# sb-sonata-debug.net
KiCad netlist of a schematic drawn in Altium Designer
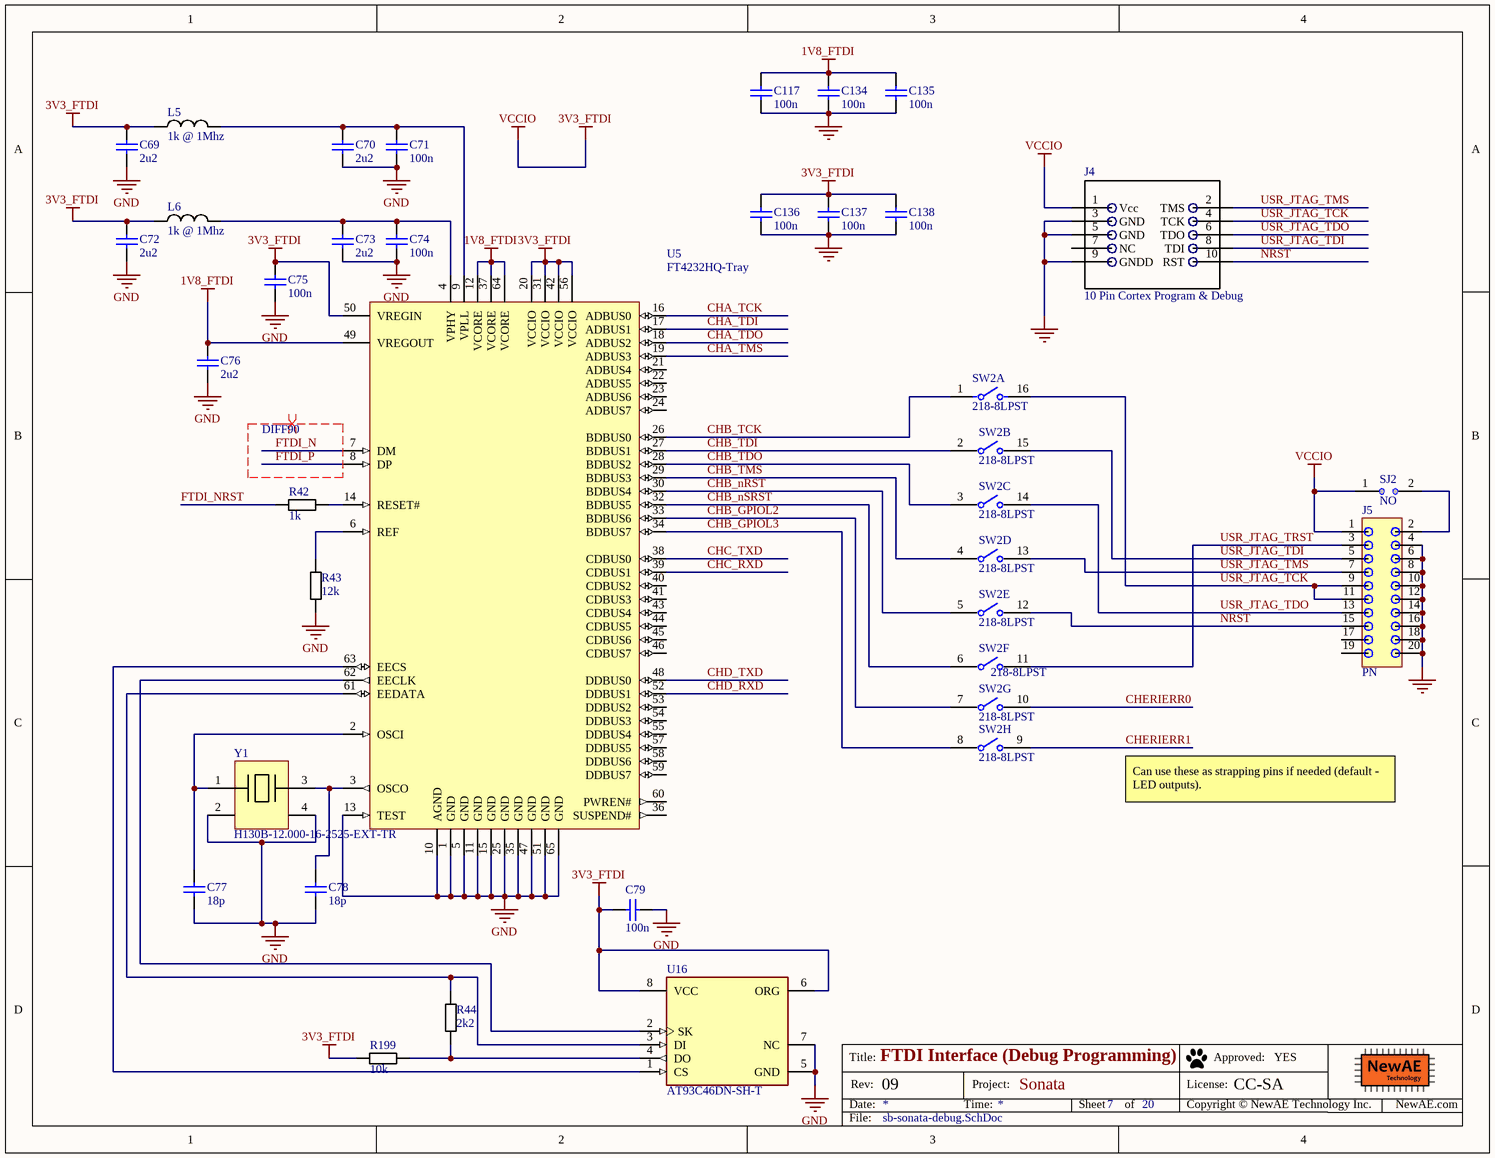
[diagram p0: sb-sonata-debug.SchDoc]

(export (version "E")
  (design (tool "Eeschema 10.0.6"))
  (components
    (comp (ref "C69")
      (value "2u2")
      (footprint "CAPC0603_M")
      (description "2u2, 0603")
      (fields (field (name "PART NUMBER") "CCHIP-2u2-0603"))
      (libsource (lib "NewAE_AltiumLib") (part "CAP"))
    )
    (comp (ref "C70")
      (value "2u2")
      (footprint "CAPC0603_M")
      (description "2u2, 0603")
      (fields (field (name "PART NUMBER") "CCHIP-2u2-0603"))
      (libsource (lib "NewAE_AltiumLib") (part "CAP"))
    )
    (comp (ref "C71")
      (value "100n")
      (footprint "CAPC0402_M")
      (description "100n, 0402")
      (fields (field (name "PART NUMBER") "CCHIP-100n-0402"))
      (libsource (lib "NewAE_AltiumLib") (part "CAP"))
    )
    (comp (ref "C72")
      (value "2u2")
      (footprint "CAPC0603_M")
      (description "2u2, 0603")
      (fields (field (name "PART NUMBER") "CCHIP-2u2-0603"))
      (libsource (lib "NewAE_AltiumLib") (part "CAP"))
    )
    (comp (ref "C73")
      (value "2u2")
      (footprint "CAPC0603_M")
      (description "2u2, 0603")
      (fields (field (name "PART NUMBER") "CCHIP-2u2-0603"))
      (libsource (lib "NewAE_AltiumLib") (part "CAP"))
    )
    (comp (ref "C74")
      (value "100n")
      (footprint "CAPC0402_M")
      (description "100n, 0402")
      (fields (field (name "PART NUMBER") "CCHIP-100n-0402"))
      (libsource (lib "NewAE_AltiumLib") (part "CAP"))
    )
    (comp (ref "C75")
      (value "100n")
      (footprint "CAPC0402_M")
      (description "100n, 0402")
      (fields (field (name "PART NUMBER") "CCHIP-100n-0402"))
      (libsource (lib "NewAE_AltiumLib") (part "CAP"))
    )
    (comp (ref "C76")
      (value "2u2")
      (footprint "CAPC0603_M")
      (description "2u2, 0603")
      (fields (field (name "PART NUMBER") "CCHIP-2u2-0603"))
      (libsource (lib "NewAE_AltiumLib") (part "CAP"))
    )
    (comp (ref "C77")
      (value "18p")
      (footprint "CAPC0402_M")
      (description "18p, 0402")
      (fields (field (name "PART NUMBER") "CCHIP-18p-0402"))
      (libsource (lib "NewAE_AltiumLib") (part "CAP"))
    )
    (comp (ref "C78")
      (value "18p")
      (footprint "CAPC0402_M")
      (description "18p, 0402")
      (fields (field (name "PART NUMBER") "CCHIP-18p-0402"))
      (libsource (lib "NewAE_AltiumLib") (part "CAP"))
    )
    (comp (ref "C79")
      (value "100n")
      (footprint "CAPC0402_M")
      (description "100n, 0402")
      (fields (field (name "PART NUMBER") "CCHIP-100n-0402"))
      (libsource (lib "NewAE_AltiumLib") (part "CAP"))
    )
    (comp (ref "C117")
      (value "100n")
      (footprint "CAPC0402_M")
      (description "100n, 0402")
      (fields (field (name "PART NUMBER") "CCHIP-100n-0402"))
      (libsource (lib "NewAE_AltiumLib") (part "CAP"))
    )
    (comp (ref "C134")
      (value "100n")
      (footprint "CAPC0402_M")
      (description "100n, 0402")
      (fields (field (name "PART NUMBER") "CCHIP-100n-0402"))
      (libsource (lib "NewAE_AltiumLib") (part "CAP"))
    )
    (comp (ref "C135")
      (value "100n")
      (footprint "CAPC0402_M")
      (description "100n, 0402")
      (fields (field (name "PART NUMBER") "CCHIP-100n-0402"))
      (libsource (lib "NewAE_AltiumLib") (part "CAP"))
    )
    (comp (ref "C136")
      (value "100n")
      (footprint "CAPC0402_M")
      (description "100n, 0402")
      (fields (field (name "PART NUMBER") "CCHIP-100n-0402"))
      (libsource (lib "NewAE_AltiumLib") (part "CAP"))
    )
    (comp (ref "C137")
      (value "100n")
      (footprint "CAPC0402_M")
      (description "100n, 0402")
      (fields (field (name "PART NUMBER") "CCHIP-100n-0402"))
      (libsource (lib "NewAE_AltiumLib") (part "CAP"))
    )
    (comp (ref "C138")
      (value "100n")
      (footprint "CAPC0402_M")
      (description "100n, 0402")
      (fields (field (name "PART NUMBER") "CCHIP-100n-0402"))
      (libsource (lib "NewAE_AltiumLib") (part "CAP"))
    )
    (comp (ref "J4")
      (value "10 Pin Cortex Program & Debug")
      (footprint "0.5mm_SMD_Header_5x2")
      (description "10 Pin Cortex Program & Debug 0.5mm pitch")
      (fields (field (name "PART NUMBER") "Cortex_Debug_Header_10Pin"))
      (libsource (lib "NewAE_AltiumLib") (part "Cortex_Debug_Header_10Pin"))
    )
    (comp (ref "J5")
      (value "PN")
      (footprint "CONN_10x2_SHROUDED_2.54mm")
      (description "Header, 2-Row, 20-pin, 0.1\"")
      (fields (field (name "PART NUMBER") "CONN20_2ROW"))
      (libsource (lib "NewAE_AltiumLib") (part "CON20_2ROW"))
    )
    (comp (ref "L5")
      (value "1k @ 1Mhz")
      (footprint "IND_0603")
      (description "Ferrite Beads HI CUR CHIP BD 0603 1000OHMS 25%")
      (fields (field (name "PART NUMBER") "FBCHIP-1k-0603"))
      (libsource (lib "NewAE_AltiumLib") (part "IND"))
    )
    (comp (ref "L6")
      (value "1k @ 1Mhz")
      (footprint "IND_0603")
      (description "Ferrite Beads HI CUR CHIP BD 0603 1000OHMS 25%")
      (fields (field (name "PART NUMBER") "FBCHIP-1k-0603"))
      (libsource (lib "NewAE_AltiumLib") (part "IND"))
    )
    (comp (ref "R42")
      (value "1k")
      (footprint "RESC1005X40N")
      (description "1k res, 0402, 1%, 1/16W")
      (fields (field (name "PART NUMBER") "RCHIP-1K-0402") (field (name "TOLERANCE") "1%"))
      (libsource (lib "") (part "RES-EU_2"))
    )
    (comp (ref "R43")
      (value "12k")
      (footprint "RESC1608X55N")
      (description "12k res, 0603, 1%, 1/10W")
      (fields (field (name "PART NUMBER") "RCHIP-12K-0603") (field (name "TOLERANCE") "1%"))
      (libsource (lib "NewAE_AltiumLib") (part "RES-EU"))
    )
    (comp (ref "R44")
      (value "2k2")
      (footprint "RESC1005X40N")
      (description "2k2 res, 0402, 1%, 1/16W")
      (fields (field (name "PART NUMBER") "RCHIP-2K2-0402") (field (name "TOLERANCE") "1%"))
      (libsource (lib "NewAE_AltiumLib") (part "RES-EU"))
    )
    (comp (ref "R199")
      (value "10k")
      (footprint "RESC1005X40N")
      (description "10k res, 0402, 1%, 1/16W")
      (fields (field (name "PART NUMBER") "RCHIP-10K-0402") (field (name "TOLERANCE") "1%"))
      (libsource (lib "") (part "RES-EU_1"))
    )
    (comp (ref "SJ2")
      (value "NO")
      (footprint "SJ_2S_NO")
      (description "Solder Jumper, NO")
      (fields (field (name "PART NUMBER") "SJ_2S_NO"))
      (libsource (lib "NewAE_AltiumLib") (part "SJ_2S_NO"))
    )
    (comp (ref "SW2")
      (value "218-8LPST")
      (footprint "FP-218-8LPST-MFG")
      (description "SWITCH SLIDE DIP SPST 25MA 24V")
      (libsource (lib "Altium Content Vault") (part "c442af63ff53b934e43635f80d8690e"))
    )
    (comp (ref "U5")
      (value "FT4232HQ-Tray")
      (footprint "QFN64_2_N")
      (description "Quad High Speed USB To Multipurpose UART/MPSSE IC, 64-pin QFN, Tray")
      (fields (field (name "MANUFACTURER") "FTDI"))
      (libsource (lib "Altium Content Vault") (part "COM-UART-FT4232H-QFN64"))
    )
    (comp (ref "U16")
      (value "AT93C46DN-SH-T")
      (footprint "FP-C04-057-SN-MFG")
      (description "IC EEPROM 1K SPI 2MHZ 8SOIC")
      (fields
        (field (name "MANUFACTURER") "Microchip")
        (field (name "OCTOPART") "https://octopart.com/at93c46dn-sh-t-microchip-77759177")
      )
      (libsource (lib "Altium Content Vault") (part "8bb9afc094b350e480db350c7247e52"))
    )
    (comp (ref "Y1")
      (value "H130B-12.000-16-2525-EXT-TR")
      (footprint "5x3.2MM XTAL")
      (description "12MHz ±25ppm Crystal 16pF 35 Ohms 4-SMD, No Lead")
      (fields (field (name "MANUFACTURER PART NUMBER") "H130B-12.000-16-2525-EXT-TR"))
      (libsource (lib "NewAE_AltiumLib") (part "H130B-12.000-16-2525-EXT-TR"))
    )
  )
  (nets
    (net (code "1") (name "/CHA_TCK") (class "Default")
      (node (ref "U5") (pin "16") (pinfunction "ADBUS0_16") (pintype "bidirectional"))
    )
    (net (code "2") (name "/CHA_TDI") (class "Default")
      (node (ref "U5") (pin "17") (pinfunction "ADBUS1_17") (pintype "bidirectional"))
    )
    (net (code "3") (name "/CHA_TDO") (class "Default")
      (node (ref "U5") (pin "18") (pinfunction "ADBUS2_18") (pintype "bidirectional"))
    )
    (net (code "4") (name "/CHA_TMS") (class "Default")
      (node (ref "U5") (pin "19") (pinfunction "ADBUS3_19") (pintype "bidirectional"))
    )
    (net (code "5") (name "/CHB_GPIOL2") (class "Default")
      (node (ref "SW2") (pin "7") (pinfunction "7_7") (pintype "passive"))
      (node (ref "U5") (pin "33") (pinfunction "BDBUS6_33") (pintype "bidirectional"))
    )
    (net (code "6") (name "/CHB_GPIOL3") (class "Default")
      (node (ref "SW2") (pin "8") (pinfunction "8_8") (pintype "passive"))
      (node (ref "U5") (pin "34") (pinfunction "BDBUS7_34") (pintype "bidirectional"))
    )
    (net (code "7") (name "/CHB_TCK") (class "Default")
      (node (ref "SW2") (pin "1") (pinfunction "1_1") (pintype "passive"))
      (node (ref "U5") (pin "26") (pinfunction "BDBUS0_26") (pintype "bidirectional"))
    )
    (net (code "8") (name "/CHB_TDI") (class "Default")
      (node (ref "SW2") (pin "2") (pinfunction "2_2") (pintype "passive"))
      (node (ref "U5") (pin "27") (pinfunction "BDBUS1_27") (pintype "bidirectional"))
    )
    (net (code "9") (name "/CHB_TDO") (class "Default")
      (node (ref "SW2") (pin "3") (pinfunction "3_3") (pintype "passive"))
      (node (ref "U5") (pin "28") (pinfunction "BDBUS2_28") (pintype "bidirectional"))
    )
    (net (code "10") (name "/CHB_TMS") (class "Default")
      (node (ref "SW2") (pin "4") (pinfunction "4_4") (pintype "passive"))
      (node (ref "U5") (pin "29") (pinfunction "BDBUS3_29") (pintype "bidirectional"))
    )
    (net (code "11") (name "/CHB_nRST") (class "Default")
      (node (ref "SW2") (pin "5") (pinfunction "5_5") (pintype "passive"))
      (node (ref "U5") (pin "30") (pinfunction "BDBUS4_30") (pintype "bidirectional"))
    )
    (net (code "12") (name "/CHB_nSRST") (class "Default")
      (node (ref "SW2") (pin "6") (pinfunction "6_6") (pintype "passive"))
      (node (ref "U5") (pin "32") (pinfunction "BDBUS5_32") (pintype "bidirectional"))
    )
    (net (code "13") (name "/CHC_RXD") (class "Default")
      (node (ref "U5") (pin "39") (pinfunction "CDBUS1_39") (pintype "bidirectional"))
    )
    (net (code "14") (name "/CHC_TXD") (class "Default")
      (node (ref "U5") (pin "38") (pinfunction "CDBUS0_38") (pintype "bidirectional"))
    )
    (net (code "15") (name "/CHD_RXD") (class "Default")
      (node (ref "U5") (pin "52") (pinfunction "DDBUS1_52") (pintype "bidirectional"))
    )
    (net (code "16") (name "/CHD_TXD") (class "Default")
      (node (ref "U5") (pin "48") (pinfunction "DDBUS0_48") (pintype "bidirectional"))
    )
    (net (code "17") (name "/CHERIERR0") (class "Default")
      (node (ref "SW2") (pin "10") (pinfunction "10_10") (pintype "passive"))
    )
    (net (code "18") (name "/CHERIERR1") (class "Default")
      (node (ref "SW2") (pin "9") (pinfunction "9_9") (pintype "passive"))
    )
    (net (code "19") (name "/FTDI_N") (class "Default")
      (node (ref "U5") (pin "7") (pinfunction "DM_7") (pintype "input"))
    )
    (net (code "20") (name "/FTDI_NRST") (class "Default")
      (node (ref "R42") (pin "2") (pinfunction "2_2") (pintype "passive"))
    )
    (net (code "21") (name "/FTDI_P") (class "Default")
      (node (ref "U5") (pin "8") (pinfunction "DP_8") (pintype "input"))
    )
    (net (code "22") (name "/NRST") (class "Default")
      (node (ref "J4") (pin "10") (pinfunction "RST_10") (pintype "passive"))
      (node (ref "J5") (pin "15") (pinfunction "9_15") (pintype "passive"))
      (node (ref "SW2") (pin "12") (pinfunction "12_12") (pintype "passive"))
    )
    (net (code "23") (name "/USR_JTAG_TCK") (class "Default")
      (node (ref "J4") (pin "4") (pinfunction "TCK_4") (pintype "passive"))
      (node (ref "J5") (pin "11") (pinfunction "9_11") (pintype "passive"))
      (node (ref "J5") (pin "9") (pinfunction "9_9") (pintype "passive"))
      (node (ref "SW2") (pin "16") (pinfunction "16_16") (pintype "passive"))
    )
    (net (code "24") (name "/USR_JTAG_TDI") (class "Default")
      (node (ref "J4") (pin "8") (pinfunction "TDI_8") (pintype "passive"))
      (node (ref "J5") (pin "5") (pinfunction "5_5") (pintype "passive"))
      (node (ref "SW2") (pin "15") (pinfunction "15_15") (pintype "passive"))
    )
    (net (code "25") (name "/USR_JTAG_TDO") (class "Default")
      (node (ref "J4") (pin "6") (pinfunction "TDO_6") (pintype "passive"))
      (node (ref "J5") (pin "13") (pinfunction "9_13") (pintype "passive"))
      (node (ref "SW2") (pin "14") (pinfunction "14_14") (pintype "passive"))
    )
    (net (code "26") (name "/USR_JTAG_TMS") (class "Default")
      (node (ref "J4") (pin "2") (pinfunction "TMS_2") (pintype "passive"))
      (node (ref "J5") (pin "7") (pinfunction "7_7") (pintype "passive"))
      (node (ref "SW2") (pin "13") (pinfunction "13_13") (pintype "passive"))
    )
    (net (code "27") (name "/USR_JTAG_TRST") (class "Default")
      (node (ref "J5") (pin "3") (pinfunction "3_3") (pintype "passive"))
      (node (ref "SW2") (pin "11") (pinfunction "11_11") (pintype "passive"))
    )
    (net (code "28") (name "1V8_FTDI") (class "Default")
      (node (ref "C117") (pin "1") (pinfunction "1_1") (pintype "passive"))
      (node (ref "C134") (pin "1") (pinfunction "1_1") (pintype "passive"))
      (node (ref "C135") (pin "1") (pinfunction "1_1") (pintype "passive"))
      (node (ref "C76") (pin "1") (pinfunction "1_1") (pintype "passive"))
      (node (ref "U5") (pin "12") (pinfunction "VCORE_12") (pintype "power_in"))
      (node (ref "U5") (pin "37") (pinfunction "VCORE_37") (pintype "power_in"))
      (node (ref "U5") (pin "49") (pinfunction "VREGOUT_49") (pintype "power_in"))
      (node (ref "U5") (pin "64") (pinfunction "VCORE_64") (pintype "power_in"))
    )
    (net (code "29") (name "3V3_FTDI") (class "Default")
      (node (ref "C136") (pin "1") (pinfunction "1_1") (pintype "passive"))
      (node (ref "C137") (pin "1") (pinfunction "1_1") (pintype "passive"))
      (node (ref "C138") (pin "1") (pinfunction "1_1") (pintype "passive"))
      (node (ref "C69") (pin "1") (pinfunction "1_1") (pintype "passive"))
      (node (ref "C72") (pin "1") (pinfunction "1_1") (pintype "passive"))
      (node (ref "C75") (pin "1") (pinfunction "1_1") (pintype "passive"))
      (node (ref "C79") (pin "1") (pinfunction "1_1") (pintype "passive"))
      (node (ref "J4") (pin "1") (pinfunction "Vcc_1") (pintype "passive"))
      (node (ref "J5") (pin "1") (pinfunction "1_1") (pintype "passive"))
      (node (ref "L5") (pin "1") (pinfunction "1_1") (pintype "passive"))
      (node (ref "L6") (pin "1") (pinfunction "1_1") (pintype "passive"))
      (node (ref "R199") (pin "1") (pinfunction "1_1") (pintype "passive"))
      (node (ref "SJ2") (pin "1") (pinfunction "1_1") (pintype "passive"))
      (node (ref "U16") (pin "6") (pinfunction "ORG_6") (pintype "passive"))
      (node (ref "U16") (pin "8") (pinfunction "VCC_8") (pintype "power_in"))
      (node (ref "U5") (pin "20") (pinfunction "VCCIO_20") (pintype "power_in"))
      (node (ref "U5") (pin "31") (pinfunction "VCCIO_31") (pintype "power_in"))
      (node (ref "U5") (pin "42") (pinfunction "VCCIO_42") (pintype "power_in"))
      (node (ref "U5") (pin "50") (pinfunction "VREGIN_50") (pintype "power_in"))
      (node (ref "U5") (pin "56") (pinfunction "VCCIO_56") (pintype "power_in"))
    )
    (net (code "30") (name "GND") (class "Default")
      (node (ref "C117") (pin "2") (pinfunction "2_2") (pintype "passive"))
      (node (ref "C134") (pin "2") (pinfunction "2_2") (pintype "passive"))
      (node (ref "C135") (pin "2") (pinfunction "2_2") (pintype "passive"))
      (node (ref "C136") (pin "2") (pinfunction "2_2") (pintype "passive"))
      (node (ref "C137") (pin "2") (pinfunction "2_2") (pintype "passive"))
      (node (ref "C138") (pin "2") (pinfunction "2_2") (pintype "passive"))
      (node (ref "C69") (pin "2") (pinfunction "2_2") (pintype "passive"))
      (node (ref "C70") (pin "2") (pinfunction "2_2") (pintype "passive"))
      (node (ref "C71") (pin "2") (pinfunction "2_2") (pintype "passive"))
      (node (ref "C72") (pin "2") (pinfunction "2_2") (pintype "passive"))
      (node (ref "C73") (pin "2") (pinfunction "2_2") (pintype "passive"))
      (node (ref "C74") (pin "2") (pinfunction "2_2") (pintype "passive"))
      (node (ref "C75") (pin "2") (pinfunction "2_2") (pintype "passive"))
      (node (ref "C76") (pin "2") (pinfunction "2_2") (pintype "passive"))
      (node (ref "C77") (pin "2") (pinfunction "2_2") (pintype "passive"))
      (node (ref "C78") (pin "2") (pinfunction "2_2") (pintype "passive"))
      (node (ref "C79") (pin "2") (pinfunction "2_2") (pintype "passive"))
      (node (ref "J4") (pin "3") (pinfunction "GND_3") (pintype "passive"))
      (node (ref "J4") (pin "5") (pinfunction "GND_5") (pintype "passive"))
      (node (ref "J4") (pin "9") (pinfunction "GNDD_9") (pintype "passive"))
      (node (ref "J5") (pin "10") (pinfunction "10_10") (pintype "passive"))
      (node (ref "J5") (pin "12") (pinfunction "10_12") (pintype "passive"))
      (node (ref "J5") (pin "14") (pinfunction "10_14") (pintype "passive"))
      (node (ref "J5") (pin "16") (pinfunction "10_16") (pintype "passive"))
      (node (ref "J5") (pin "18") (pinfunction "10_18") (pintype "passive"))
      (node (ref "J5") (pin "20") (pinfunction "10_20") (pintype "passive"))
      (node (ref "J5") (pin "4") (pinfunction "4_4") (pintype "passive"))
      (node (ref "J5") (pin "6") (pinfunction "6_6") (pintype "passive"))
      (node (ref "J5") (pin "8") (pinfunction "8_8") (pintype "passive"))
      (node (ref "R43") (pin "2") (pinfunction "2_2") (pintype "passive"))
      (node (ref "U16") (pin "5") (pinfunction "GND_5") (pintype "power_in"))
      (node (ref "U16") (pin "7") (pinfunction "NC_7") (pintype "passive"))
      (node (ref "U5") (pin "1") (pinfunction "GND_1") (pintype "power_in"))
      (node (ref "U5") (pin "10") (pinfunction "AGND_10") (pintype "power_in"))
      (node (ref "U5") (pin "11") (pinfunction "GND_11") (pintype "power_in"))
      (node (ref "U5") (pin "13") (pinfunction "TEST_13") (pintype "input"))
      (node (ref "U5") (pin "15") (pinfunction "GND_15") (pintype "power_in"))
      (node (ref "U5") (pin "25") (pinfunction "GND_25") (pintype "power_in"))
      (node (ref "U5") (pin "35") (pinfunction "GND_35") (pintype "power_in"))
      (node (ref "U5") (pin "47") (pinfunction "GND_47") (pintype "power_in"))
      (node (ref "U5") (pin "5") (pinfunction "GND_5") (pintype "power_in"))
      (node (ref "U5") (pin "51") (pinfunction "GND_51") (pintype "power_in"))
      (node (ref "U5") (pin "65") (pinfunction "GND_65") (pintype "power_in"))
      (node (ref "Y1") (pin "2") (pinfunction "2_2") (pintype "passive"))
      (node (ref "Y1") (pin "4") (pinfunction "4_4") (pintype "passive"))
    )
    (net (code "31") (name "Net-(J5-Pad2)") (class "Default")
      (node (ref "J5") (pin "2") (pinfunction "2_2") (pintype "passive"))
      (node (ref "SJ2") (pin "2") (pinfunction "2_2") (pintype "passive"))
    )
    (net (code "32") (name "Net-(U5-OSCI)") (class "Default")
      (node (ref "C77") (pin "1") (pinfunction "1_1") (pintype "passive"))
      (node (ref "U5") (pin "2") (pinfunction "OSCI_2") (pintype "input"))
      (node (ref "Y1") (pin "1") (pinfunction "1_1") (pintype "passive"))
    )
    (net (code "33") (name "Net-(U5-OSCO)") (class "Default")
      (node (ref "C78") (pin "1") (pinfunction "1_1") (pintype "passive"))
      (node (ref "U5") (pin "3") (pinfunction "OSCO_3") (pintype "output"))
      (node (ref "Y1") (pin "3") (pinfunction "3_3") (pintype "passive"))
    )
    (net (code "34") (name "Net-(U5-REF)") (class "Default")
      (node (ref "R43") (pin "1") (pinfunction "1_1") (pintype "passive"))
      (node (ref "U5") (pin "6") (pinfunction "REF_6") (pintype "input"))
    )
    (net (code "35") (name "Net-(U5-RESET#)") (class "Default")
      (node (ref "R42") (pin "1") (pinfunction "1_1") (pintype "passive"))
      (node (ref "U5") (pin "14") (pinfunction "RESET#_14") (pintype "input"))
    )
    (net (code "36") (name "Net-(U5-VPHY)") (class "Default")
      (node (ref "C73") (pin "1") (pinfunction "1_1") (pintype "passive"))
      (node (ref "C74") (pin "1") (pinfunction "1_1") (pintype "passive"))
      (node (ref "L6") (pin "2") (pinfunction "2_2") (pintype "passive"))
      (node (ref "U5") (pin "4") (pinfunction "VPHY_4") (pintype "power_in"))
    )
    (net (code "37") (name "Net-(U5-VPLL)") (class "Default")
      (node (ref "C70") (pin "1") (pinfunction "1_1") (pintype "passive"))
      (node (ref "C71") (pin "1") (pinfunction "1_1") (pintype "passive"))
      (node (ref "L5") (pin "2") (pinfunction "2_2") (pintype "passive"))
      (node (ref "U5") (pin "9") (pinfunction "VPLL_9") (pintype "power_in"))
    )
    (net (code "38") (name "Net-(U16-CS)") (class "Default")
      (node (ref "U16") (pin "1") (pinfunction "CS_1") (pintype "input"))
      (node (ref "U5") (pin "63") (pinfunction "EECS_63") (pintype "bidirectional"))
    )
    (net (code "39") (name "Net-(U16-DI)") (class "Default")
      (node (ref "R44") (pin "1") (pinfunction "1_1") (pintype "passive"))
      (node (ref "U16") (pin "3") (pinfunction "DI_3") (pintype "input"))
      (node (ref "U5") (pin "61") (pinfunction "EEDATA_61") (pintype "bidirectional"))
    )
    (net (code "40") (name "Net-(U16-DO)") (class "Default")
      (node (ref "R199") (pin "2") (pinfunction "2_2") (pintype "passive"))
      (node (ref "R44") (pin "2") (pinfunction "2_2") (pintype "passive"))
      (node (ref "U16") (pin "4") (pinfunction "DO_4") (pintype "output"))
    )
    (net (code "41") (name "Net-(U16-SK)") (class "Default")
      (node (ref "U16") (pin "2") (pinfunction "SK_2") (pintype "input"))
      (node (ref "U5") (pin "62") (pinfunction "EECLK_62") (pintype "output"))
    )
    (net (code "42") (name "unconnected-(J4-NC-Pad7)") (class "Default")
      (node (ref "J4") (pin "7") (pinfunction "NC_7") (pintype "passive"))
    )
    (net (code "43") (name "unconnected-(J5-9-Pad17)") (class "Default")
      (node (ref "J5") (pin "17") (pinfunction "9_17") (pintype "passive"))
    )
    (net (code "44") (name "unconnected-(J5-9-Pad19)") (class "Default")
      (node (ref "J5") (pin "19") (pinfunction "9_19") (pintype "passive"))
    )
    (net (code "45") (name "unconnected-(U5-ADBUS4-Pad21)") (class "Default")
      (node (ref "U5") (pin "21") (pinfunction "ADBUS4_21") (pintype "bidirectional"))
    )
    (net (code "46") (name "unconnected-(U5-ADBUS5-Pad22)") (class "Default")
      (node (ref "U5") (pin "22") (pinfunction "ADBUS5_22") (pintype "bidirectional"))
    )
    (net (code "47") (name "unconnected-(U5-ADBUS6-Pad23)") (class "Default")
      (node (ref "U5") (pin "23") (pinfunction "ADBUS6_23") (pintype "bidirectional"))
    )
    (net (code "48") (name "unconnected-(U5-ADBUS7-Pad24)") (class "Default")
      (node (ref "U5") (pin "24") (pinfunction "ADBUS7_24") (pintype "bidirectional"))
    )
    (net (code "49") (name "unconnected-(U5-CDBUS2-Pad40)") (class "Default")
      (node (ref "U5") (pin "40") (pinfunction "CDBUS2_40") (pintype "bidirectional"))
    )
    (net (code "50") (name "unconnected-(U5-CDBUS3-Pad41)") (class "Default")
      (node (ref "U5") (pin "41") (pinfunction "CDBUS3_41") (pintype "bidirectional"))
    )
    (net (code "51") (name "unconnected-(U5-CDBUS4-Pad43)") (class "Default")
      (node (ref "U5") (pin "43") (pinfunction "CDBUS4_43") (pintype "bidirectional"))
    )
    (net (code "52") (name "unconnected-(U5-CDBUS5-Pad44)") (class "Default")
      (node (ref "U5") (pin "44") (pinfunction "CDBUS5_44") (pintype "bidirectional"))
    )
    (net (code "53") (name "unconnected-(U5-CDBUS6-Pad45)") (class "Default")
      (node (ref "U5") (pin "45") (pinfunction "CDBUS6_45") (pintype "bidirectional"))
    )
    (net (code "54") (name "unconnected-(U5-CDBUS7-Pad46)") (class "Default")
      (node (ref "U5") (pin "46") (pinfunction "CDBUS7_46") (pintype "bidirectional"))
    )
    (net (code "55") (name "unconnected-(U5-DDBUS2-Pad53)") (class "Default")
      (node (ref "U5") (pin "53") (pinfunction "DDBUS2_53") (pintype "bidirectional"))
    )
    (net (code "56") (name "unconnected-(U5-DDBUS3-Pad54)") (class "Default")
      (node (ref "U5") (pin "54") (pinfunction "DDBUS3_54") (pintype "bidirectional"))
    )
    (net (code "57") (name "unconnected-(U5-DDBUS4-Pad55)") (class "Default")
      (node (ref "U5") (pin "55") (pinfunction "DDBUS4_55") (pintype "bidirectional"))
    )
    (net (code "58") (name "unconnected-(U5-DDBUS5-Pad57)") (class "Default")
      (node (ref "U5") (pin "57") (pinfunction "DDBUS5_57") (pintype "bidirectional"))
    )
    (net (code "59") (name "unconnected-(U5-DDBUS6-Pad58)") (class "Default")
      (node (ref "U5") (pin "58") (pinfunction "DDBUS6_58") (pintype "bidirectional"))
    )
    (net (code "60") (name "unconnected-(U5-DDBUS7-Pad59)") (class "Default")
      (node (ref "U5") (pin "59") (pinfunction "DDBUS7_59") (pintype "bidirectional"))
    )
    (net (code "61") (name "unconnected-(U5-PWREN#-Pad60)") (class "Default")
      (node (ref "U5") (pin "60") (pinfunction "PWREN#_60") (pintype "output"))
    )
    (net (code "62") (name "unconnected-(U5-SUSPEND#-Pad36)") (class "Default")
      (node (ref "U5") (pin "36") (pinfunction "SUSPEND#_36") (pintype "output"))
    )
  )
)
